# relay_block.net
KiCad netlist of a schematic drawn in EAGLE
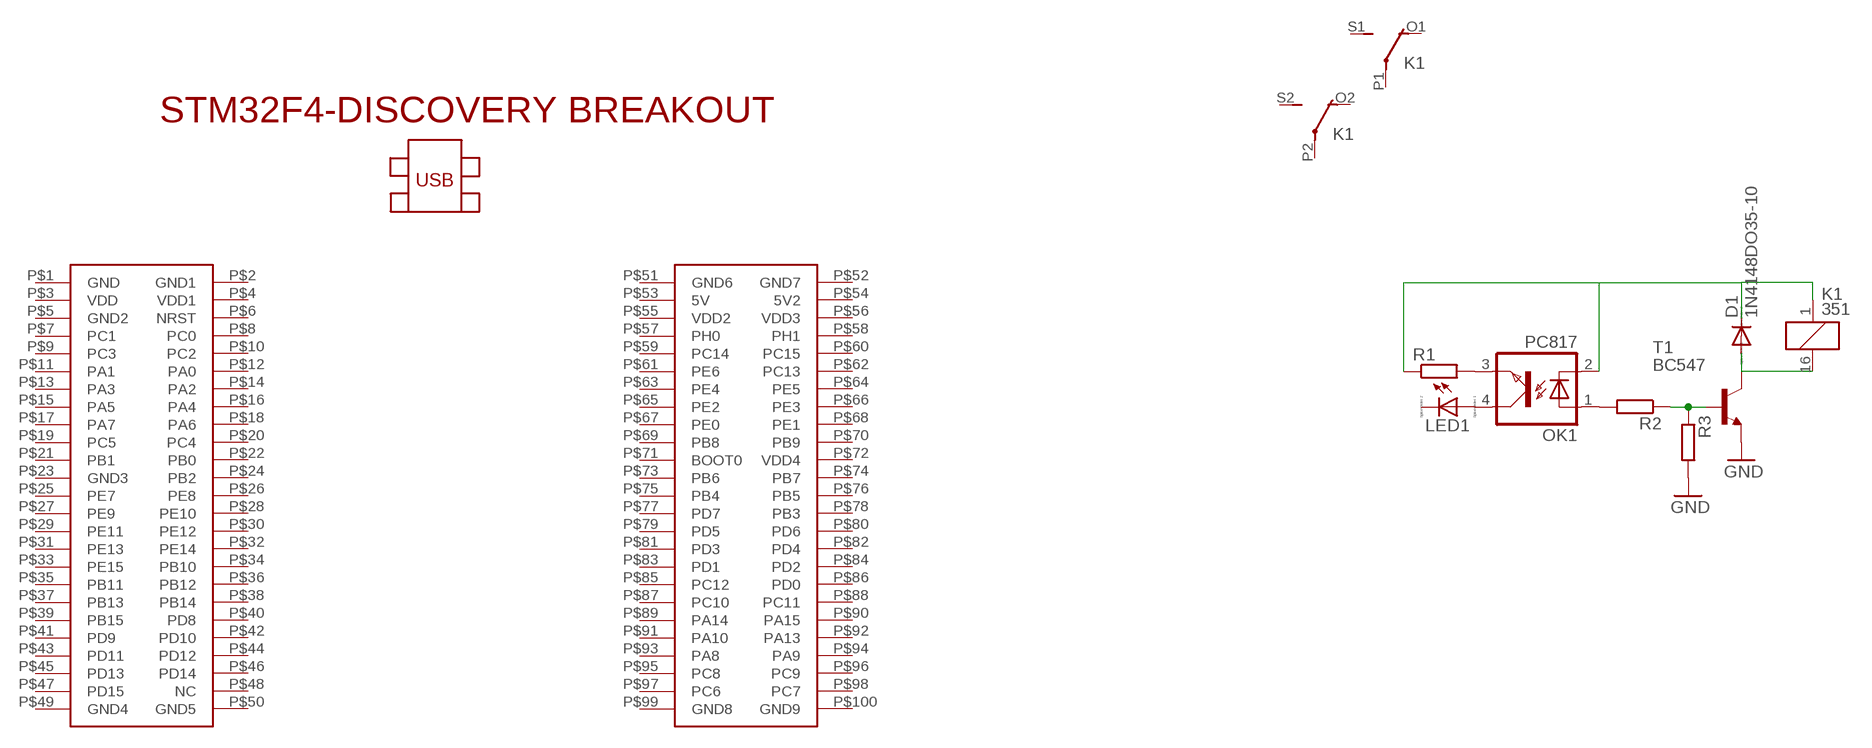
[diagram p0: schematic, sheet 1]

(export (version "E")
  (design (tool "Eeschema 10.0.6"))
  (components
    (comp (ref "D1")
      (value "1N4148DO35-10")
      (footprint "eagle-import:DO35-10")
      (libsource (lib "eagle-import") (part "1N4148DO35-10"))
    )
    (comp (ref "K1")
      (value "351")
      (footprint "eagle-import:351")
      (libsource (lib "eagle-import") (part "351"))
    )
    (comp (ref "LED1")
      (value "LED_ELD260")
      (footprint "eagle-import:LED_LD260")
      (libsource (lib "eagle-import") (part "LED_ELD260"))
    )
    (comp (ref "OK1")
      (value "PC817")
      (footprint "eagle-import:DIL04")
      (fields (field (name "MPN") "PC817X4J000F"))
      (libsource (lib "eagle-import") (part "PC817"))
    )
    (comp (ref "R1")
      (value "R-EU_M1206")
      (footprint "eagle-import:M1206")
      (libsource (lib "eagle-import") (part "R-EU_M1206"))
    )
    (comp (ref "R2")
      (value "R-EU_M1206")
      (footprint "eagle-import:M1206")
      (libsource (lib "eagle-import") (part "R-EU_M1206"))
    )
    (comp (ref "R3")
      (value "R-EU_M1206")
      (footprint "eagle-import:M1206")
      (libsource (lib "eagle-import") (part "R-EU_M1206"))
    )
    (comp (ref "T1")
      (value "BC547")
      (footprint "eagle-import:TO92")
      (libsource (lib "eagle-import") (part "BC547"))
    )
    (comp (ref "U$1")
      (value "STM32F4-DISCOVERY_STM32F4-DISCOVERY")
      (footprint "eagle-import:STM32F4-DISCOVERY_STM32F4-DISCOVERY")
      (libsource (lib "eagle-import") (part "STM32F4-DISCOVERY_STM32F4-DISCOVERY"))
    )
  )
  (nets
    (net (code "1") (name "GND") (class "Default")
      (node (ref "R3") (pin "2") (pinfunction "2_2") (pintype "passive"))
      (node (ref "T1") (pin "1") (pinfunction "E_1") (pintype "passive"))
    )
    (net (code "2") (name "Net-(K1A-2)") (class "Default")
      (node (ref "D1") (pin "A") (pinfunction "A_A") (pintype "passive"))
      (node (ref "K1") (pin "16") (pinfunction "2_16") (pintype "passive"))
      (node (ref "T1") (pin "3") (pinfunction "C_3") (pintype "passive"))
    )
    (net (code "3") (name "Net-(OK1-A)") (class "Default")
      (node (ref "OK1") (pin "1") (pinfunction "A_1") (pintype "passive"))
      (node (ref "R2") (pin "2") (pinfunction "2_2") (pintype "passive"))
    )
    (net (code "4") (name "Net-(OK1-C)") (class "Default")
      (node (ref "D1") (pin "C") (pinfunction "C_C") (pintype "passive"))
      (node (ref "K1") (pin "1") (pinfunction "1_1") (pintype "passive"))
      (node (ref "OK1") (pin "2") (pinfunction "C_2") (pintype "passive"))
      (node (ref "R1") (pin "1") (pinfunction "1_1") (pintype "passive"))
    )
    (net (code "5") (name "Net-(OK1-COL)") (class "Default")
      (node (ref "LED1") (pin "A") (pinfunction "A_A") (pintype "passive"))
      (node (ref "OK1") (pin "4") (pinfunction "COL_4") (pintype "passive"))
    )
    (net (code "6") (name "Net-(OK1-EMIT)") (class "Default")
      (node (ref "OK1") (pin "3") (pinfunction "EMIT_3") (pintype "passive"))
      (node (ref "R1") (pin "2") (pinfunction "2_2") (pintype "passive"))
    )
    (net (code "7") (name "Net-(T1-B)") (class "Default")
      (node (ref "R2") (pin "1") (pinfunction "1_1") (pintype "passive"))
      (node (ref "R3") (pin "1") (pinfunction "1_1") (pintype "passive"))
      (node (ref "T1") (pin "2") (pinfunction "B_2") (pintype "passive"))
    )
    (net (code "8") (name "unconnected-(K1B-O-PadO1)") (class "Default")
      (node (ref "K1") (pin "O1") (pinfunction "O_O1") (pintype "passive"))
    )
    (net (code "9") (name "unconnected-(K1B-P-PadP1)") (class "Default")
      (node (ref "K1") (pin "P1") (pinfunction "P_P1") (pintype "passive"))
    )
    (net (code "10") (name "unconnected-(K1B-S-PadS1)") (class "Default")
      (node (ref "K1") (pin "S1") (pinfunction "S_S1") (pintype "passive"))
    )
    (net (code "11") (name "unconnected-(K1C-O-PadO2)") (class "Default")
      (node (ref "K1") (pin "O2") (pinfunction "O_O2") (pintype "passive"))
    )
    (net (code "12") (name "unconnected-(K1C-P-PadP2)") (class "Default")
      (node (ref "K1") (pin "P2") (pinfunction "P_P2") (pintype "passive"))
    )
    (net (code "13") (name "unconnected-(K1C-S-PadS2)") (class "Default")
      (node (ref "K1") (pin "S2") (pinfunction "S_S2") (pintype "passive"))
    )
    (net (code "14") (name "unconnected-(LED1-C-PadK)") (class "Default")
      (node (ref "LED1") (pin "K") (pinfunction "C_K") (pintype "passive"))
    )
    (net (code "15") (name "unconnected-(U$1-5V-PadP$53)") (class "Default")
      (node (ref "U$1") (pin "P$53") (pinfunction "5V_P$53") (pintype "bidirectional"))
    )
    (net (code "16") (name "unconnected-(U$1-5V2-PadP$54)") (class "Default")
      (node (ref "U$1") (pin "P$54") (pinfunction "5V2_P$54") (pintype "bidirectional"))
    )
    (net (code "17") (name "unconnected-(U$1-BOOT0-PadP$71)") (class "Default")
      (node (ref "U$1") (pin "P$71") (pinfunction "BOOT0_P$71") (pintype "bidirectional"))
    )
    (net (code "18") (name "unconnected-(U$1-GND-PadP$1)") (class "Default")
      (node (ref "U$1") (pin "P$1") (pinfunction "GND_P$1") (pintype "bidirectional"))
    )
    (net (code "19") (name "unconnected-(U$1-GND1-PadP$2)") (class "Default")
      (node (ref "U$1") (pin "P$2") (pinfunction "GND1_P$2") (pintype "bidirectional"))
    )
    (net (code "20") (name "unconnected-(U$1-GND2-PadP$5)") (class "Default")
      (node (ref "U$1") (pin "P$5") (pinfunction "GND2_P$5") (pintype "bidirectional"))
    )
    (net (code "21") (name "unconnected-(U$1-GND3-PadP$23)") (class "Default")
      (node (ref "U$1") (pin "P$23") (pinfunction "GND3_P$23") (pintype "bidirectional"))
    )
    (net (code "22") (name "unconnected-(U$1-GND4-PadP$49)") (class "Default")
      (node (ref "U$1") (pin "P$49") (pinfunction "GND4_P$49") (pintype "bidirectional"))
    )
    (net (code "23") (name "unconnected-(U$1-GND5-PadP$50)") (class "Default")
      (node (ref "U$1") (pin "P$50") (pinfunction "GND5_P$50") (pintype "bidirectional"))
    )
    (net (code "24") (name "unconnected-(U$1-GND6-PadP$51)") (class "Default")
      (node (ref "U$1") (pin "P$51") (pinfunction "GND6_P$51") (pintype "bidirectional"))
    )
    (net (code "25") (name "unconnected-(U$1-GND7-PadP$52)") (class "Default")
      (node (ref "U$1") (pin "P$52") (pinfunction "GND7_P$52") (pintype "bidirectional"))
    )
    (net (code "26") (name "unconnected-(U$1-GND8-PadP$99)") (class "Default")
      (node (ref "U$1") (pin "P$99") (pinfunction "GND8_P$99") (pintype "bidirectional"))
    )
    (net (code "27") (name "unconnected-(U$1-GND9-PadP$100)") (class "Default")
      (node (ref "U$1") (pin "P$100") (pinfunction "GND9_P$100") (pintype "bidirectional"))
    )
    (net (code "28") (name "unconnected-(U$1-NC-PadP$48)") (class "Default")
      (node (ref "U$1") (pin "P$48") (pinfunction "NC_P$48") (pintype "bidirectional"))
    )
    (net (code "29") (name "unconnected-(U$1-NRST-PadP$6)") (class "Default")
      (node (ref "U$1") (pin "P$6") (pinfunction "NRST_P$6") (pintype "bidirectional"))
    )
    (net (code "30") (name "unconnected-(U$1-PA0-PadP$12)") (class "Default")
      (node (ref "U$1") (pin "P$12") (pinfunction "PA0_P$12") (pintype "bidirectional"))
    )
    (net (code "31") (name "unconnected-(U$1-PA1-PadP$11)") (class "Default")
      (node (ref "U$1") (pin "P$11") (pinfunction "PA1_P$11") (pintype "bidirectional"))
    )
    (net (code "32") (name "unconnected-(U$1-PA2-PadP$14)") (class "Default")
      (node (ref "U$1") (pin "P$14") (pinfunction "PA2_P$14") (pintype "bidirectional"))
    )
    (net (code "33") (name "unconnected-(U$1-PA3-PadP$13)") (class "Default")
      (node (ref "U$1") (pin "P$13") (pinfunction "PA3_P$13") (pintype "bidirectional"))
    )
    (net (code "34") (name "unconnected-(U$1-PA4-PadP$16)") (class "Default")
      (node (ref "U$1") (pin "P$16") (pinfunction "PA4_P$16") (pintype "bidirectional"))
    )
    (net (code "35") (name "unconnected-(U$1-PA5-PadP$15)") (class "Default")
      (node (ref "U$1") (pin "P$15") (pinfunction "PA5_P$15") (pintype "bidirectional"))
    )
    (net (code "36") (name "unconnected-(U$1-PA6-PadP$18)") (class "Default")
      (node (ref "U$1") (pin "P$18") (pinfunction "PA6_P$18") (pintype "bidirectional"))
    )
    (net (code "37") (name "unconnected-(U$1-PA7-PadP$17)") (class "Default")
      (node (ref "U$1") (pin "P$17") (pinfunction "PA7_P$17") (pintype "bidirectional"))
    )
    (net (code "38") (name "unconnected-(U$1-PA8-PadP$93)") (class "Default")
      (node (ref "U$1") (pin "P$93") (pinfunction "PA8_P$93") (pintype "bidirectional"))
    )
    (net (code "39") (name "unconnected-(U$1-PA9-PadP$94)") (class "Default")
      (node (ref "U$1") (pin "P$94") (pinfunction "PA9_P$94") (pintype "bidirectional"))
    )
    (net (code "40") (name "unconnected-(U$1-PA10-PadP$91)") (class "Default")
      (node (ref "U$1") (pin "P$91") (pinfunction "PA10_P$91") (pintype "bidirectional"))
    )
    (net (code "41") (name "unconnected-(U$1-PA13-PadP$92)") (class "Default")
      (node (ref "U$1") (pin "P$92") (pinfunction "PA13_P$92") (pintype "bidirectional"))
    )
    (net (code "42") (name "unconnected-(U$1-PA14-PadP$89)") (class "Default")
      (node (ref "U$1") (pin "P$89") (pinfunction "PA14_P$89") (pintype "bidirectional"))
    )
    (net (code "43") (name "unconnected-(U$1-PA15-PadP$90)") (class "Default")
      (node (ref "U$1") (pin "P$90") (pinfunction "PA15_P$90") (pintype "bidirectional"))
    )
    (net (code "44") (name "unconnected-(U$1-PB0-PadP$22)") (class "Default")
      (node (ref "U$1") (pin "P$22") (pinfunction "PB0_P$22") (pintype "bidirectional"))
    )
    (net (code "45") (name "unconnected-(U$1-PB1-PadP$21)") (class "Default")
      (node (ref "U$1") (pin "P$21") (pinfunction "PB1_P$21") (pintype "bidirectional"))
    )
    (net (code "46") (name "unconnected-(U$1-PB2-PadP$24)") (class "Default")
      (node (ref "U$1") (pin "P$24") (pinfunction "PB2_P$24") (pintype "bidirectional"))
    )
    (net (code "47") (name "unconnected-(U$1-PB3-PadP$78)") (class "Default")
      (node (ref "U$1") (pin "P$78") (pinfunction "PB3_P$78") (pintype "bidirectional"))
    )
    (net (code "48") (name "unconnected-(U$1-PB4-PadP$75)") (class "Default")
      (node (ref "U$1") (pin "P$75") (pinfunction "PB4_P$75") (pintype "bidirectional"))
    )
    (net (code "49") (name "unconnected-(U$1-PB5-PadP$76)") (class "Default")
      (node (ref "U$1") (pin "P$76") (pinfunction "PB5_P$76") (pintype "bidirectional"))
    )
    (net (code "50") (name "unconnected-(U$1-PB6-PadP$73)") (class "Default")
      (node (ref "U$1") (pin "P$73") (pinfunction "PB6_P$73") (pintype "bidirectional"))
    )
    (net (code "51") (name "unconnected-(U$1-PB7-PadP$74)") (class "Default")
      (node (ref "U$1") (pin "P$74") (pinfunction "PB7_P$74") (pintype "bidirectional"))
    )
    (net (code "52") (name "unconnected-(U$1-PB8-PadP$69)") (class "Default")
      (node (ref "U$1") (pin "P$69") (pinfunction "PB8_P$69") (pintype "bidirectional"))
    )
    (net (code "53") (name "unconnected-(U$1-PB9-PadP$70)") (class "Default")
      (node (ref "U$1") (pin "P$70") (pinfunction "PB9_P$70") (pintype "bidirectional"))
    )
    (net (code "54") (name "unconnected-(U$1-PB10-PadP$34)") (class "Default")
      (node (ref "U$1") (pin "P$34") (pinfunction "PB10_P$34") (pintype "bidirectional"))
    )
    (net (code "55") (name "unconnected-(U$1-PB11-PadP$35)") (class "Default")
      (node (ref "U$1") (pin "P$35") (pinfunction "PB11_P$35") (pintype "bidirectional"))
    )
    (net (code "56") (name "unconnected-(U$1-PB12-PadP$36)") (class "Default")
      (node (ref "U$1") (pin "P$36") (pinfunction "PB12_P$36") (pintype "bidirectional"))
    )
    (net (code "57") (name "unconnected-(U$1-PB13-PadP$37)") (class "Default")
      (node (ref "U$1") (pin "P$37") (pinfunction "PB13_P$37") (pintype "bidirectional"))
    )
    (net (code "58") (name "unconnected-(U$1-PB14-PadP$38)") (class "Default")
      (node (ref "U$1") (pin "P$38") (pinfunction "PB14_P$38") (pintype "bidirectional"))
    )
    (net (code "59") (name "unconnected-(U$1-PB15-PadP$39)") (class "Default")
      (node (ref "U$1") (pin "P$39") (pinfunction "PB15_P$39") (pintype "bidirectional"))
    )
    (net (code "60") (name "unconnected-(U$1-PC0-PadP$8)") (class "Default")
      (node (ref "U$1") (pin "P$8") (pinfunction "PC0_P$8") (pintype "bidirectional"))
    )
    (net (code "61") (name "unconnected-(U$1-PC1-PadP$7)") (class "Default")
      (node (ref "U$1") (pin "P$7") (pinfunction "PC1_P$7") (pintype "bidirectional"))
    )
    (net (code "62") (name "unconnected-(U$1-PC2-PadP$10)") (class "Default")
      (node (ref "U$1") (pin "P$10") (pinfunction "PC2_P$10") (pintype "bidirectional"))
    )
    (net (code "63") (name "unconnected-(U$1-PC3-PadP$9)") (class "Default")
      (node (ref "U$1") (pin "P$9") (pinfunction "PC3_P$9") (pintype "bidirectional"))
    )
    (net (code "64") (name "unconnected-(U$1-PC4-PadP$20)") (class "Default")
      (node (ref "U$1") (pin "P$20") (pinfunction "PC4_P$20") (pintype "bidirectional"))
    )
    (net (code "65") (name "unconnected-(U$1-PC5-PadP$19)") (class "Default")
      (node (ref "U$1") (pin "P$19") (pinfunction "PC5_P$19") (pintype "bidirectional"))
    )
    (net (code "66") (name "unconnected-(U$1-PC6-PadP$97)") (class "Default")
      (node (ref "U$1") (pin "P$97") (pinfunction "PC6_P$97") (pintype "bidirectional"))
    )
    (net (code "67") (name "unconnected-(U$1-PC7-PadP$98)") (class "Default")
      (node (ref "U$1") (pin "P$98") (pinfunction "PC7_P$98") (pintype "bidirectional"))
    )
    (net (code "68") (name "unconnected-(U$1-PC8-PadP$95)") (class "Default")
      (node (ref "U$1") (pin "P$95") (pinfunction "PC8_P$95") (pintype "bidirectional"))
    )
    (net (code "69") (name "unconnected-(U$1-PC9-PadP$96)") (class "Default")
      (node (ref "U$1") (pin "P$96") (pinfunction "PC9_P$96") (pintype "bidirectional"))
    )
    (net (code "70") (name "unconnected-(U$1-PC10-PadP$87)") (class "Default")
      (node (ref "U$1") (pin "P$87") (pinfunction "PC10_P$87") (pintype "bidirectional"))
    )
    (net (code "71") (name "unconnected-(U$1-PC11-PadP$88)") (class "Default")
      (node (ref "U$1") (pin "P$88") (pinfunction "PC11_P$88") (pintype "bidirectional"))
    )
    (net (code "72") (name "unconnected-(U$1-PC12-PadP$85)") (class "Default")
      (node (ref "U$1") (pin "P$85") (pinfunction "PC12_P$85") (pintype "bidirectional"))
    )
    (net (code "73") (name "unconnected-(U$1-PC13-PadP$62)") (class "Default")
      (node (ref "U$1") (pin "P$62") (pinfunction "PC13_P$62") (pintype "bidirectional"))
    )
    (net (code "74") (name "unconnected-(U$1-PC14-PadP$59)") (class "Default")
      (node (ref "U$1") (pin "P$59") (pinfunction "PC14_P$59") (pintype "bidirectional"))
    )
    (net (code "75") (name "unconnected-(U$1-PC15-PadP$60)") (class "Default")
      (node (ref "U$1") (pin "P$60") (pinfunction "PC15_P$60") (pintype "bidirectional"))
    )
    (net (code "76") (name "unconnected-(U$1-PD0-PadP$86)") (class "Default")
      (node (ref "U$1") (pin "P$86") (pinfunction "PD0_P$86") (pintype "bidirectional"))
    )
    (net (code "77") (name "unconnected-(U$1-PD1-PadP$83)") (class "Default")
      (node (ref "U$1") (pin "P$83") (pinfunction "PD1_P$83") (pintype "bidirectional"))
    )
    (net (code "78") (name "unconnected-(U$1-PD2-PadP$84)") (class "Default")
      (node (ref "U$1") (pin "P$84") (pinfunction "PD2_P$84") (pintype "bidirectional"))
    )
    (net (code "79") (name "unconnected-(U$1-PD3-PadP$81)") (class "Default")
      (node (ref "U$1") (pin "P$81") (pinfunction "PD3_P$81") (pintype "bidirectional"))
    )
    (net (code "80") (name "unconnected-(U$1-PD4-PadP$82)") (class "Default")
      (node (ref "U$1") (pin "P$82") (pinfunction "PD4_P$82") (pintype "bidirectional"))
    )
    (net (code "81") (name "unconnected-(U$1-PD5-PadP$79)") (class "Default")
      (node (ref "U$1") (pin "P$79") (pinfunction "PD5_P$79") (pintype "bidirectional"))
    )
    (net (code "82") (name "unconnected-(U$1-PD6-PadP$80)") (class "Default")
      (node (ref "U$1") (pin "P$80") (pinfunction "PD6_P$80") (pintype "bidirectional"))
    )
    (net (code "83") (name "unconnected-(U$1-PD7-PadP$77)") (class "Default")
      (node (ref "U$1") (pin "P$77") (pinfunction "PD7_P$77") (pintype "bidirectional"))
    )
    (net (code "84") (name "unconnected-(U$1-PD8-PadP$40)") (class "Default")
      (node (ref "U$1") (pin "P$40") (pinfunction "PD8_P$40") (pintype "bidirectional"))
    )
    (net (code "85") (name "unconnected-(U$1-PD9-PadP$41)") (class "Default")
      (node (ref "U$1") (pin "P$41") (pinfunction "PD9_P$41") (pintype "bidirectional"))
    )
    (net (code "86") (name "unconnected-(U$1-PD10-PadP$42)") (class "Default")
      (node (ref "U$1") (pin "P$42") (pinfunction "PD10_P$42") (pintype "bidirectional"))
    )
    (net (code "87") (name "unconnected-(U$1-PD11-PadP$43)") (class "Default")
      (node (ref "U$1") (pin "P$43") (pinfunction "PD11_P$43") (pintype "bidirectional"))
    )
    (net (code "88") (name "unconnected-(U$1-PD12-PadP$44)") (class "Default")
      (node (ref "U$1") (pin "P$44") (pinfunction "PD12_P$44") (pintype "bidirectional"))
    )
    (net (code "89") (name "unconnected-(U$1-PD13-PadP$45)") (class "Default")
      (node (ref "U$1") (pin "P$45") (pinfunction "PD13_P$45") (pintype "bidirectional"))
    )
    (net (code "90") (name "unconnected-(U$1-PD14-PadP$46)") (class "Default")
      (node (ref "U$1") (pin "P$46") (pinfunction "PD14_P$46") (pintype "bidirectional"))
    )
    (net (code "91") (name "unconnected-(U$1-PD15-PadP$47)") (class "Default")
      (node (ref "U$1") (pin "P$47") (pinfunction "PD15_P$47") (pintype "bidirectional"))
    )
    (net (code "92") (name "unconnected-(U$1-PE0-PadP$67)") (class "Default")
      (node (ref "U$1") (pin "P$67") (pinfunction "PE0_P$67") (pintype "bidirectional"))
    )
    (net (code "93") (name "unconnected-(U$1-PE1-PadP$68)") (class "Default")
      (node (ref "U$1") (pin "P$68") (pinfunction "PE1_P$68") (pintype "bidirectional"))
    )
    (net (code "94") (name "unconnected-(U$1-PE2-PadP$65)") (class "Default")
      (node (ref "U$1") (pin "P$65") (pinfunction "PE2_P$65") (pintype "bidirectional"))
    )
    (net (code "95") (name "unconnected-(U$1-PE3-PadP$66)") (class "Default")
      (node (ref "U$1") (pin "P$66") (pinfunction "PE3_P$66") (pintype "bidirectional"))
    )
    (net (code "96") (name "unconnected-(U$1-PE4-PadP$63)") (class "Default")
      (node (ref "U$1") (pin "P$63") (pinfunction "PE4_P$63") (pintype "bidirectional"))
    )
    (net (code "97") (name "unconnected-(U$1-PE5-PadP$64)") (class "Default")
      (node (ref "U$1") (pin "P$64") (pinfunction "PE5_P$64") (pintype "bidirectional"))
    )
    (net (code "98") (name "unconnected-(U$1-PE6-PadP$61)") (class "Default")
      (node (ref "U$1") (pin "P$61") (pinfunction "PE6_P$61") (pintype "bidirectional"))
    )
    (net (code "99") (name "unconnected-(U$1-PE7-PadP$25)") (class "Default")
      (node (ref "U$1") (pin "P$25") (pinfunction "PE7_P$25") (pintype "bidirectional"))
    )
    (net (code "100") (name "unconnected-(U$1-PE8-PadP$26)") (class "Default")
      (node (ref "U$1") (pin "P$26") (pinfunction "PE8_P$26") (pintype "bidirectional"))
    )
    (net (code "101") (name "unconnected-(U$1-PE9-PadP$27)") (class "Default")
      (node (ref "U$1") (pin "P$27") (pinfunction "PE9_P$27") (pintype "bidirectional"))
    )
    (net (code "102") (name "unconnected-(U$1-PE10-PadP$28)") (class "Default")
      (node (ref "U$1") (pin "P$28") (pinfunction "PE10_P$28") (pintype "bidirectional"))
    )
    (net (code "103") (name "unconnected-(U$1-PE11-PadP$29)") (class "Default")
      (node (ref "U$1") (pin "P$29") (pinfunction "PE11_P$29") (pintype "bidirectional"))
    )
    (net (code "104") (name "unconnected-(U$1-PE12-PadP$30)") (class "Default")
      (node (ref "U$1") (pin "P$30") (pinfunction "PE12_P$30") (pintype "bidirectional"))
    )
    (net (code "105") (name "unconnected-(U$1-PE13-PadP$31)") (class "Default")
      (node (ref "U$1") (pin "P$31") (pinfunction "PE13_P$31") (pintype "bidirectional"))
    )
    (net (code "106") (name "unconnected-(U$1-PE14-PadP$32)") (class "Default")
      (node (ref "U$1") (pin "P$32") (pinfunction "PE14_P$32") (pintype "bidirectional"))
    )
    (net (code "107") (name "unconnected-(U$1-PE15-PadP$33)") (class "Default")
      (node (ref "U$1") (pin "P$33") (pinfunction "PE15_P$33") (pintype "bidirectional"))
    )
    (net (code "108") (name "unconnected-(U$1-PH0-PadP$57)") (class "Default")
      (node (ref "U$1") (pin "P$57") (pinfunction "PH0_P$57") (pintype "bidirectional"))
    )
    (net (code "109") (name "unconnected-(U$1-PH1-PadP$58)") (class "Default")
      (node (ref "U$1") (pin "P$58") (pinfunction "PH1_P$58") (pintype "bidirectional"))
    )
    (net (code "110") (name "unconnected-(U$1-VDD-PadP$3)") (class "Default")
      (node (ref "U$1") (pin "P$3") (pinfunction "VDD_P$3") (pintype "bidirectional"))
    )
    (net (code "111") (name "unconnected-(U$1-VDD1-PadP$4)") (class "Default")
      (node (ref "U$1") (pin "P$4") (pinfunction "VDD1_P$4") (pintype "bidirectional"))
    )
    (net (code "112") (name "unconnected-(U$1-VDD2-PadP$55)") (class "Default")
      (node (ref "U$1") (pin "P$55") (pinfunction "VDD2_P$55") (pintype "bidirectional"))
    )
    (net (code "113") (name "unconnected-(U$1-VDD3-PadP$56)") (class "Default")
      (node (ref "U$1") (pin "P$56") (pinfunction "VDD3_P$56") (pintype "bidirectional"))
    )
    (net (code "114") (name "unconnected-(U$1-VDD4-PadP$72)") (class "Default")
      (node (ref "U$1") (pin "P$72") (pinfunction "VDD4_P$72") (pintype "bidirectional"))
    )
  )
)
